# ET-FPGAIO.net
KiCad netlist of a schematic drawn in Altium Designer
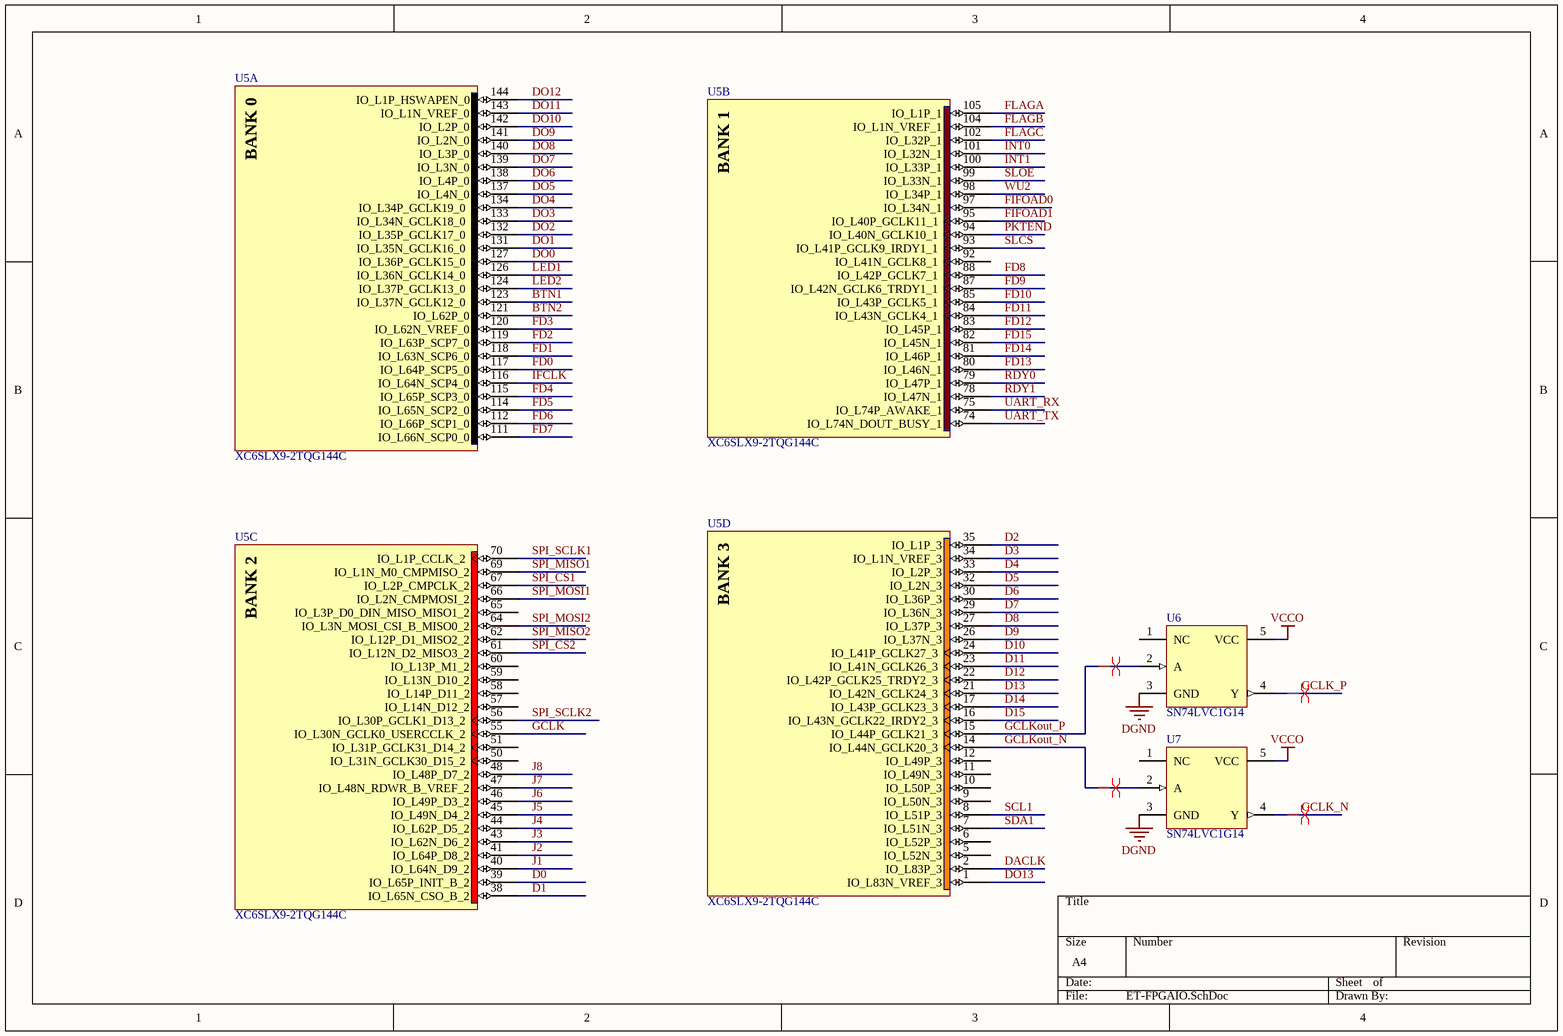
[diagram p0: ET-FPGAIO.SchDoc]

(export (version "E")
  (design (tool "Eeschema 10.0.6"))
  (components
    (comp (ref "U5")
      (value "XC6SLX9-2TQG144C")
      (footprint "TQG144_N")
      (fields (field (name "PUBLISHER") "Altium Limited"))
      (libsource (lib "Xilinx Spartan-6") (part "XC6SLX9-2TQG144C"))
    )
    (comp (ref "U6")
      (value "SN74LVC1G14")
      (footprint "SOT-23-5")
      (libsource (lib "My Library") (part "SN74LVC1G14"))
    )
    (comp (ref "U7")
      (value "SN74LVC1G14")
      (footprint "SOT-23-5")
      (libsource (lib "My Library") (part "SN74LVC1G14"))
    )
  )
  (nets
    (net (code "1") (name "/BTN1") (class "Default")
      (node (ref "U5") (pin "123") (pinfunction "IO_L37N_GCLK12_0_123") (pintype "bidirectional"))
    )
    (net (code "2") (name "/BTN2") (class "Default")
      (node (ref "U5") (pin "121") (pinfunction "IO_L62P_0_121") (pintype "bidirectional"))
    )
    (net (code "3") (name "/D0") (class "Default")
      (node (ref "U5") (pin "39") (pinfunction "IO_L65P_INIT_B_2_39") (pintype "bidirectional"))
    )
    (net (code "4") (name "/D1") (class "Default")
      (node (ref "U5") (pin "38") (pinfunction "IO_L65N_CSO_B_2_38") (pintype "bidirectional"))
    )
    (net (code "5") (name "/D2") (class "Default")
      (node (ref "U5") (pin "35") (pinfunction "IO_L1P_3_35") (pintype "bidirectional"))
    )
    (net (code "6") (name "/D3") (class "Default")
      (node (ref "U5") (pin "34") (pinfunction "IO_L1N_VREF_3_34") (pintype "bidirectional"))
    )
    (net (code "7") (name "/D4") (class "Default")
      (node (ref "U5") (pin "33") (pinfunction "IO_L2P_3_33") (pintype "bidirectional"))
    )
    (net (code "8") (name "/D5") (class "Default")
      (node (ref "U5") (pin "32") (pinfunction "IO_L2N_3_32") (pintype "bidirectional"))
    )
    (net (code "9") (name "/D6") (class "Default")
      (node (ref "U5") (pin "30") (pinfunction "IO_L36P_3_30") (pintype "bidirectional"))
    )
    (net (code "10") (name "/D7") (class "Default")
      (node (ref "U5") (pin "29") (pinfunction "IO_L36N_3_29") (pintype "bidirectional"))
    )
    (net (code "11") (name "/D8") (class "Default")
      (node (ref "U5") (pin "27") (pinfunction "IO_L37P_3_27") (pintype "bidirectional"))
    )
    (net (code "12") (name "/D9") (class "Default")
      (node (ref "U5") (pin "26") (pinfunction "IO_L37N_3_26") (pintype "bidirectional"))
    )
    (net (code "13") (name "/D10") (class "Default")
      (node (ref "U5") (pin "24") (pinfunction "IO_L41P_GCLK27_3_24") (pintype "bidirectional"))
    )
    (net (code "14") (name "/D11") (class "Default")
      (node (ref "U5") (pin "23") (pinfunction "IO_L41N_GCLK26_3_23") (pintype "bidirectional"))
    )
    (net (code "15") (name "/D12") (class "Default")
      (node (ref "U5") (pin "22") (pinfunction "IO_L42P_GCLK25_TRDY2_3_22") (pintype "bidirectional"))
    )
    (net (code "16") (name "/D13") (class "Default")
      (node (ref "U5") (pin "21") (pinfunction "IO_L42N_GCLK24_3_21") (pintype "bidirectional"))
    )
    (net (code "17") (name "/D14") (class "Default")
      (node (ref "U5") (pin "17") (pinfunction "IO_L43P_GCLK23_3_17") (pintype "bidirectional"))
    )
    (net (code "18") (name "/D15") (class "Default")
      (node (ref "U5") (pin "16") (pinfunction "IO_L43N_GCLK22_IRDY2_3_16") (pintype "bidirectional"))
    )
    (net (code "19") (name "/DACLK") (class "Default")
      (node (ref "U5") (pin "2") (pinfunction "IO_L83P_3_2") (pintype "bidirectional"))
    )
    (net (code "20") (name "/DO0") (class "Default")
      (node (ref "U5") (pin "127") (pinfunction "IO_L36P_GCLK15_0_127") (pintype "bidirectional"))
    )
    (net (code "21") (name "/DO1") (class "Default")
      (node (ref "U5") (pin "131") (pinfunction "IO_L35N_GCLK16_0_131") (pintype "bidirectional"))
    )
    (net (code "22") (name "/DO2") (class "Default")
      (node (ref "U5") (pin "132") (pinfunction "IO_L35P_GCLK17_0_132") (pintype "bidirectional"))
    )
    (net (code "23") (name "/DO3") (class "Default")
      (node (ref "U5") (pin "133") (pinfunction "IO_L34N_GCLK18_0_133") (pintype "bidirectional"))
    )
    (net (code "24") (name "/DO4") (class "Default")
      (node (ref "U5") (pin "134") (pinfunction "IO_L34P_GCLK19_0_134") (pintype "bidirectional"))
    )
    (net (code "25") (name "/DO5") (class "Default")
      (node (ref "U5") (pin "137") (pinfunction "IO_L4N_0_137") (pintype "bidirectional"))
    )
    (net (code "26") (name "/DO6") (class "Default")
      (node (ref "U5") (pin "138") (pinfunction "IO_L4P_0_138") (pintype "bidirectional"))
    )
    (net (code "27") (name "/DO7") (class "Default")
      (node (ref "U5") (pin "139") (pinfunction "IO_L3N_0_139") (pintype "bidirectional"))
    )
    (net (code "28") (name "/DO8") (class "Default")
      (node (ref "U5") (pin "140") (pinfunction "IO_L3P_0_140") (pintype "bidirectional"))
    )
    (net (code "29") (name "/DO9") (class "Default")
      (node (ref "U5") (pin "141") (pinfunction "IO_L2N_0_141") (pintype "bidirectional"))
    )
    (net (code "30") (name "/DO10") (class "Default")
      (node (ref "U5") (pin "142") (pinfunction "IO_L2P_0_142") (pintype "bidirectional"))
    )
    (net (code "31") (name "/DO11") (class "Default")
      (node (ref "U5") (pin "143") (pinfunction "IO_L1N_VREF_0_143") (pintype "bidirectional"))
    )
    (net (code "32") (name "/DO12") (class "Default")
      (node (ref "U5") (pin "144") (pinfunction "IO_L1P_HSWAPEN_0_144") (pintype "bidirectional"))
    )
    (net (code "33") (name "/DO13") (class "Default")
      (node (ref "U5") (pin "1") (pinfunction "IO_L83N_VREF_3_1") (pintype "bidirectional"))
    )
    (net (code "34") (name "/FD0") (class "Default")
      (node (ref "U5") (pin "117") (pinfunction "IO_L64P_SCP5_0_117") (pintype "bidirectional"))
    )
    (net (code "35") (name "/FD1") (class "Default")
      (node (ref "U5") (pin "118") (pinfunction "IO_L63N_SCP6_0_118") (pintype "bidirectional"))
    )
    (net (code "36") (name "/FD2") (class "Default")
      (node (ref "U5") (pin "119") (pinfunction "IO_L63P_SCP7_0_119") (pintype "bidirectional"))
    )
    (net (code "37") (name "/FD3") (class "Default")
      (node (ref "U5") (pin "120") (pinfunction "IO_L62N_VREF_0_120") (pintype "bidirectional"))
    )
    (net (code "38") (name "/FD4") (class "Default")
      (node (ref "U5") (pin "115") (pinfunction "IO_L65P_SCP3_0_115") (pintype "bidirectional"))
    )
    (net (code "39") (name "/FD5") (class "Default")
      (node (ref "U5") (pin "114") (pinfunction "IO_L65N_SCP2_0_114") (pintype "bidirectional"))
    )
    (net (code "40") (name "/FD6") (class "Default")
      (node (ref "U5") (pin "112") (pinfunction "IO_L66P_SCP1_0_112") (pintype "bidirectional"))
    )
    (net (code "41") (name "/FD7") (class "Default")
      (node (ref "U5") (pin "111") (pinfunction "IO_L66N_SCP0_0_111") (pintype "bidirectional"))
    )
    (net (code "42") (name "/FD8") (class "Default")
      (node (ref "U5") (pin "88") (pinfunction "IO_L42P_GCLK7_1_88") (pintype "bidirectional"))
    )
    (net (code "43") (name "/FD9") (class "Default")
      (node (ref "U5") (pin "87") (pinfunction "IO_L42N_GCLK6_TRDY1_1_87") (pintype "bidirectional"))
    )
    (net (code "44") (name "/FD10") (class "Default")
      (node (ref "U5") (pin "85") (pinfunction "IO_L43P_GCLK5_1_85") (pintype "bidirectional"))
    )
    (net (code "45") (name "/FD11") (class "Default")
      (node (ref "U5") (pin "84") (pinfunction "IO_L43N_GCLK4_1_84") (pintype "bidirectional"))
    )
    (net (code "46") (name "/FD12") (class "Default")
      (node (ref "U5") (pin "83") (pinfunction "IO_L45P_1_83") (pintype "bidirectional"))
    )
    (net (code "47") (name "/FD13") (class "Default")
      (node (ref "U5") (pin "80") (pinfunction "IO_L46N_1_80") (pintype "bidirectional"))
    )
    (net (code "48") (name "/FD14") (class "Default")
      (node (ref "U5") (pin "81") (pinfunction "IO_L46P_1_81") (pintype "bidirectional"))
    )
    (net (code "49") (name "/FD15") (class "Default")
      (node (ref "U5") (pin "82") (pinfunction "IO_L45N_1_82") (pintype "bidirectional"))
    )
    (net (code "50") (name "/FIFOAD0") (class "Default")
      (node (ref "U5") (pin "97") (pinfunction "IO_L34N_1_97") (pintype "bidirectional"))
    )
    (net (code "51") (name "/FIFOAD1") (class "Default")
      (node (ref "U5") (pin "95") (pinfunction "IO_L40P_GCLK11_1_95") (pintype "bidirectional"))
    )
    (net (code "52") (name "/FLAGA") (class "Default")
      (node (ref "U5") (pin "105") (pinfunction "IO_L1P_1_105") (pintype "bidirectional"))
    )
    (net (code "53") (name "/FLAGB") (class "Default")
      (node (ref "U5") (pin "104") (pinfunction "IO_L1N_VREF_1_104") (pintype "bidirectional"))
    )
    (net (code "54") (name "/FLAGC") (class "Default")
      (node (ref "U5") (pin "102") (pinfunction "IO_L32P_1_102") (pintype "bidirectional"))
    )
    (net (code "55") (name "/GCLK") (class "Default")
      (node (ref "U5") (pin "55") (pinfunction "IO_L30N_GCLK0_USERCCLK_2_55") (pintype "bidirectional"))
    )
    (net (code "56") (name "/GCLK_N") (class "Default")
      (node (ref "U7") (pin "4") (pinfunction "Y_4") (pintype "output"))
    )
    (net (code "57") (name "/GCLK_P") (class "Default")
      (node (ref "U6") (pin "4") (pinfunction "Y_4") (pintype "output"))
    )
    (net (code "58") (name "/GCLKout_N") (class "Default")
      (node (ref "U5") (pin "14") (pinfunction "IO_L44N_GCLK20_3_14") (pintype "bidirectional"))
      (node (ref "U7") (pin "2") (pinfunction "A_2") (pintype "input"))
    )
    (net (code "59") (name "/GCLKout_P") (class "Default")
      (node (ref "U5") (pin "15") (pinfunction "IO_L44P_GCLK21_3_15") (pintype "bidirectional"))
      (node (ref "U6") (pin "2") (pinfunction "A_2") (pintype "input"))
    )
    (net (code "60") (name "/IFCLK") (class "Default")
      (node (ref "U5") (pin "116") (pinfunction "IO_L64N_SCP4_0_116") (pintype "bidirectional"))
    )
    (net (code "61") (name "/J1") (class "Default")
      (node (ref "U5") (pin "40") (pinfunction "IO_L64N_D9_2_40") (pintype "bidirectional"))
    )
    (net (code "62") (name "/J2") (class "Default")
      (node (ref "U5") (pin "41") (pinfunction "IO_L64P_D8_2_41") (pintype "bidirectional"))
    )
    (net (code "63") (name "/J3") (class "Default")
      (node (ref "U5") (pin "43") (pinfunction "IO_L62N_D6_2_43") (pintype "bidirectional"))
    )
    (net (code "64") (name "/J4") (class "Default")
      (node (ref "U5") (pin "44") (pinfunction "IO_L62P_D5_2_44") (pintype "bidirectional"))
    )
    (net (code "65") (name "/J5") (class "Default")
      (node (ref "U5") (pin "45") (pinfunction "IO_L49N_D4_2_45") (pintype "bidirectional"))
    )
    (net (code "66") (name "/J6") (class "Default")
      (node (ref "U5") (pin "46") (pinfunction "IO_L49P_D3_2_46") (pintype "bidirectional"))
    )
    (net (code "67") (name "/J7") (class "Default")
      (node (ref "U5") (pin "47") (pinfunction "IO_L48N_RDWR_B_VREF_2_47") (pintype "bidirectional"))
    )
    (net (code "68") (name "/J8") (class "Default")
      (node (ref "U5") (pin "48") (pinfunction "IO_L48P_D7_2_48") (pintype "bidirectional"))
    )
    (net (code "69") (name "/LED1") (class "Default")
      (node (ref "U5") (pin "126") (pinfunction "IO_L36N_GCLK14_0_126") (pintype "bidirectional"))
    )
    (net (code "70") (name "/LED2") (class "Default")
      (node (ref "U5") (pin "124") (pinfunction "IO_L37P_GCLK13_0_124") (pintype "bidirectional"))
    )
    (net (code "71") (name "/PKTEND") (class "Default")
      (node (ref "U5") (pin "94") (pinfunction "IO_L40N_GCLK10_1_94") (pintype "bidirectional"))
    )
    (net (code "72") (name "/RDY0") (class "Default")
      (node (ref "U5") (pin "79") (pinfunction "IO_L47P_1_79") (pintype "bidirectional"))
    )
    (net (code "73") (name "/RDY1") (class "Default")
      (node (ref "U5") (pin "78") (pinfunction "IO_L47N_1_78") (pintype "bidirectional"))
    )
    (net (code "74") (name "/SCL1") (class "Default")
      (node (ref "U5") (pin "8") (pinfunction "IO_L51P_3_8") (pintype "bidirectional"))
    )
    (net (code "75") (name "/SDA1") (class "Default")
      (node (ref "U5") (pin "7") (pinfunction "IO_L51N_3_7") (pintype "bidirectional"))
    )
    (net (code "76") (name "/SLOE") (class "Default")
      (node (ref "U5") (pin "99") (pinfunction "IO_L33N_1_99") (pintype "bidirectional"))
    )
    (net (code "77") (name "/SPI_CS1") (class "Default")
      (node (ref "U5") (pin "67") (pinfunction "IO_L2P_CMPCLK_2_67") (pintype "bidirectional"))
    )
    (net (code "78") (name "/SPI_CS2") (class "Default")
      (node (ref "U5") (pin "61") (pinfunction "IO_L12N_D2_MISO3_2_61") (pintype "bidirectional"))
    )
    (net (code "79") (name "/SPI_MISO1") (class "Default")
      (node (ref "U5") (pin "69") (pinfunction "IO_L1N_M0_CMPMISO_2_69") (pintype "bidirectional"))
    )
    (net (code "80") (name "/SPI_MISO2") (class "Default")
      (node (ref "U5") (pin "62") (pinfunction "IO_L12P_D1_MISO2_2_62") (pintype "bidirectional"))
    )
    (net (code "81") (name "/SPI_MOSI1") (class "Default")
      (node (ref "U5") (pin "66") (pinfunction "IO_L2N_CMPMOSI_2_66") (pintype "bidirectional"))
    )
    (net (code "82") (name "/SPI_MOSI2") (class "Default")
      (node (ref "U5") (pin "64") (pinfunction "IO_L3N_MOSI_CSI_B_MISO0_2_64") (pintype "bidirectional"))
    )
    (net (code "83") (name "/SPI_SCLK1") (class "Default")
      (node (ref "U5") (pin "70") (pinfunction "IO_L1P_CCLK_2_70") (pintype "bidirectional"))
    )
    (net (code "84") (name "/SPI_SCLK2") (class "Default")
      (node (ref "U5") (pin "56") (pinfunction "IO_L30P_GCLK1_D13_2_56") (pintype "bidirectional"))
    )
    (net (code "85") (name "/UART_RX") (class "Default")
      (node (ref "U5") (pin "75") (pinfunction "IO_L74P_AWAKE_1_75") (pintype "bidirectional"))
    )
    (net (code "86") (name "/UART_TX") (class "Default")
      (node (ref "U5") (pin "74") (pinfunction "IO_L74N_DOUT_BUSY_1_74") (pintype "bidirectional"))
    )
    (net (code "87") (name "/WU2") (class "Default")
      (node (ref "U5") (pin "98") (pinfunction "IO_L34P_1_98") (pintype "bidirectional"))
    )
    (net (code "88") (name "/~{INT0}") (class "Default")
      (node (ref "U5") (pin "101") (pinfunction "IO_L32N_1_101") (pintype "bidirectional"))
    )
    (net (code "89") (name "/~{INT1}") (class "Default")
      (node (ref "U5") (pin "100") (pinfunction "IO_L33P_1_100") (pintype "bidirectional"))
    )
    (net (code "90") (name "/~{SLCS}") (class "Default")
      (node (ref "U5") (pin "93") (pinfunction "IO_L41P_GCLK9_IRDY1_1_93") (pintype "bidirectional"))
    )
    (net (code "91") (name "DGND") (class "Default")
      (node (ref "U6") (pin "3") (pinfunction "GND_3") (pintype "open_collector"))
      (node (ref "U7") (pin "3") (pinfunction "GND_3") (pintype "open_collector"))
    )
    (net (code "92") (name "VCCO") (class "Default")
      (node (ref "U6") (pin "5") (pinfunction "VCC_5") (pintype "power_in"))
      (node (ref "U7") (pin "5") (pinfunction "VCC_5") (pintype "power_in"))
    )
    (net (code "93") (name "unconnected-(U5B-IO_L41N_GCLK8_1-Pad92)") (class "Default")
      (node (ref "U5") (pin "92") (pinfunction "IO_L41N_GCLK8_1_92") (pintype "bidirectional"))
    )
    (net (code "94") (name "unconnected-(U5C-IO_L3P_D0_DIN_MISO_MISO1_2-Pad65)") (class "Default")
      (node (ref "U5") (pin "65") (pinfunction "IO_L3P_D0_DIN_MISO_MISO1_2_65") (pintype "bidirectional"))
    )
    (net (code "95") (name "unconnected-(U5C-IO_L13N_D10_2-Pad59)") (class "Default")
      (node (ref "U5") (pin "59") (pinfunction "IO_L13N_D10_2_59") (pintype "bidirectional"))
    )
    (net (code "96") (name "unconnected-(U5C-IO_L13P_M1_2-Pad60)") (class "Default")
      (node (ref "U5") (pin "60") (pinfunction "IO_L13P_M1_2_60") (pintype "bidirectional"))
    )
    (net (code "97") (name "unconnected-(U5C-IO_L14N_D12_2-Pad57)") (class "Default")
      (node (ref "U5") (pin "57") (pinfunction "IO_L14N_D12_2_57") (pintype "bidirectional"))
    )
    (net (code "98") (name "unconnected-(U5C-IO_L14P_D11_2-Pad58)") (class "Default")
      (node (ref "U5") (pin "58") (pinfunction "IO_L14P_D11_2_58") (pintype "bidirectional"))
    )
    (net (code "99") (name "unconnected-(U5C-IO_L31N_GCLK30_D15_2-Pad50)") (class "Default")
      (node (ref "U5") (pin "50") (pinfunction "IO_L31N_GCLK30_D15_2_50") (pintype "bidirectional"))
    )
    (net (code "100") (name "unconnected-(U5C-IO_L31P_GCLK31_D14_2-Pad51)") (class "Default")
      (node (ref "U5") (pin "51") (pinfunction "IO_L31P_GCLK31_D14_2_51") (pintype "bidirectional"))
    )
    (net (code "101") (name "unconnected-(U5D-IO_L49N_3-Pad11)") (class "Default")
      (node (ref "U5") (pin "11") (pinfunction "IO_L49N_3_11") (pintype "bidirectional"))
    )
    (net (code "102") (name "unconnected-(U5D-IO_L49P_3-Pad12)") (class "Default")
      (node (ref "U5") (pin "12") (pinfunction "IO_L49P_3_12") (pintype "bidirectional"))
    )
    (net (code "103") (name "unconnected-(U5D-IO_L50N_3-Pad9)") (class "Default")
      (node (ref "U5") (pin "9") (pinfunction "IO_L50N_3_9") (pintype "bidirectional"))
    )
    (net (code "104") (name "unconnected-(U5D-IO_L50P_3-Pad10)") (class "Default")
      (node (ref "U5") (pin "10") (pinfunction "IO_L50P_3_10") (pintype "bidirectional"))
    )
    (net (code "105") (name "unconnected-(U5D-IO_L52N_3-Pad5)") (class "Default")
      (node (ref "U5") (pin "5") (pinfunction "IO_L52N_3_5") (pintype "bidirectional"))
    )
    (net (code "106") (name "unconnected-(U5D-IO_L52P_3-Pad6)") (class "Default")
      (node (ref "U5") (pin "6") (pinfunction "IO_L52P_3_6") (pintype "bidirectional"))
    )
    (net (code "107") (name "unconnected-(U6-NC-Pad1)") (class "Default")
      (node (ref "U6") (pin "1") (pinfunction "NC_1") (pintype "open_collector"))
    )
    (net (code "108") (name "unconnected-(U7-NC-Pad1)") (class "Default")
      (node (ref "U7") (pin "1") (pinfunction "NC_1") (pintype "open_collector"))
    )
  )
)
